# bluepill.net
KiCad netlist of a schematic drawn in EAGLE
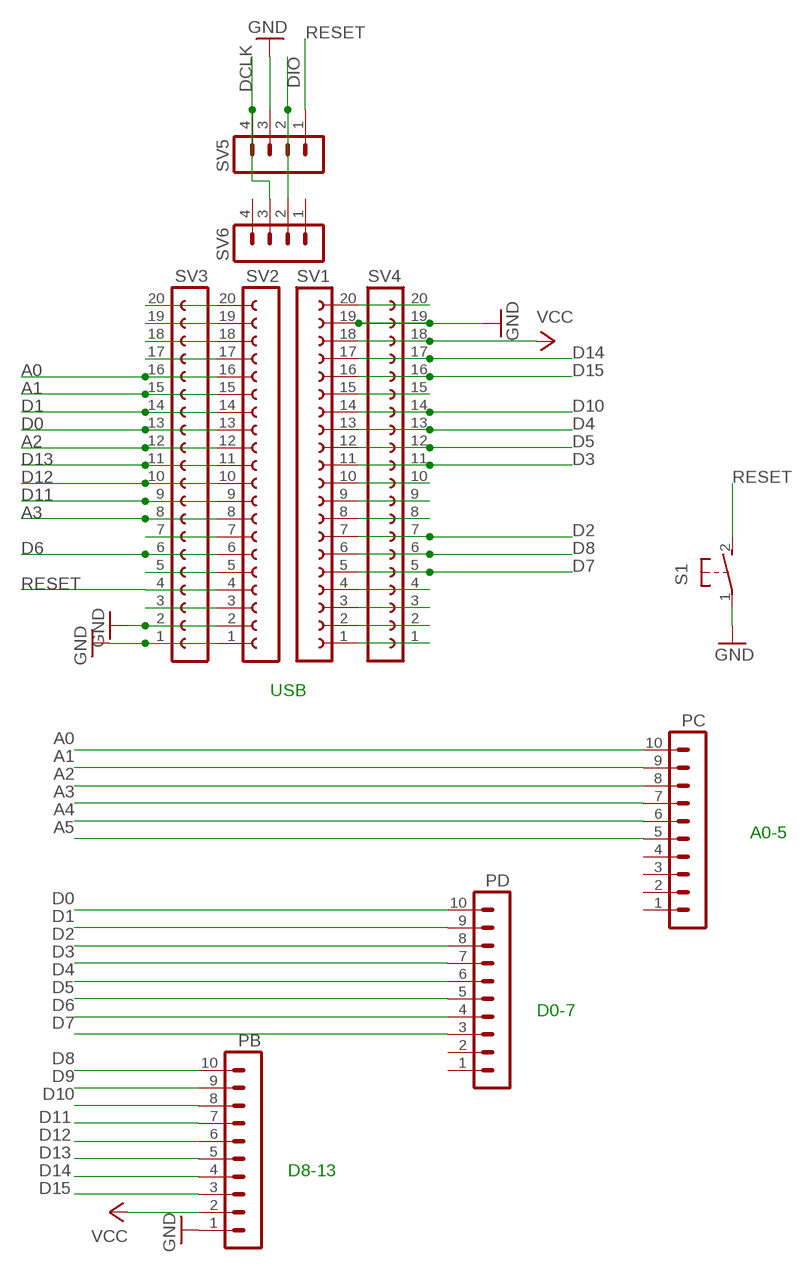
[diagram p0: schematic, sheet 1]

(export (version "E")
  (design (tool "Eeschema 10.0.6"))
  (components
    (comp (ref "PB")
      (value "MA10-1W")
      (footprint "eagle-import:MA10-1W")
      (libsource (lib "eagle-import") (part "MA10-1W"))
    )
    (comp (ref "PC")
      (value "MA10-1W")
      (footprint "eagle-import:MA10-1W")
      (libsource (lib "eagle-import") (part "MA10-1W"))
    )
    (comp (ref "PD")
      (value "MA10-1W")
      (footprint "eagle-import:MA10-1W")
      (libsource (lib "eagle-import") (part "MA10-1W"))
    )
    (comp (ref "S1")
      (value "31-XX")
      (footprint "eagle-import:B3F-31XX")
      (fields (field (name "MPN") "B3F-3100"))
      (libsource (lib "eagle-import") (part "31-XX"))
    )
    (comp (ref "SV1")
      (value "FE20-1")
      (footprint "eagle-import:FE20")
      (libsource (lib "eagle-import") (part "FE20-1"))
    )
    (comp (ref "SV2")
      (value "FE20-1")
      (footprint "eagle-import:FE20")
      (libsource (lib "eagle-import") (part "FE20-1"))
    )
    (comp (ref "SV3")
      (value "FE20-1")
      (footprint "eagle-import:FE20")
      (libsource (lib "eagle-import") (part "FE20-1"))
    )
    (comp (ref "SV4")
      (value "FE20-1")
      (footprint "eagle-import:FE20")
      (libsource (lib "eagle-import") (part "FE20-1"))
    )
    (comp (ref "SV5")
      (value "MA04-1")
      (footprint "eagle-import:MA04-1")
      (libsource (lib "eagle-import") (part "MA04-1"))
    )
    (comp (ref "SV6")
      (value "MA04-1")
      (footprint "eagle-import:MA04-1")
      (libsource (lib "eagle-import") (part "MA04-1"))
    )
  )
  (nets
    (net (code "1") (name "/A0") (class "Default")
      (node (ref "PC") (pin "10") (pinfunction "10_10") (pintype "passive"))
      (node (ref "SV2") (pin "16") (pinfunction "16_16") (pintype "passive"))
      (node (ref "SV3") (pin "16") (pinfunction "16_16") (pintype "passive"))
    )
    (net (code "2") (name "/A1") (class "Default")
      (node (ref "PC") (pin "9") (pinfunction "9_9") (pintype "passive"))
      (node (ref "SV2") (pin "15") (pinfunction "15_15") (pintype "passive"))
      (node (ref "SV3") (pin "15") (pinfunction "15_15") (pintype "passive"))
    )
    (net (code "3") (name "/A2") (class "Default")
      (node (ref "PC") (pin "8") (pinfunction "8_8") (pintype "passive"))
      (node (ref "SV2") (pin "12") (pinfunction "12_12") (pintype "passive"))
      (node (ref "SV3") (pin "12") (pinfunction "12_12") (pintype "passive"))
    )
    (net (code "4") (name "/A3") (class "Default")
      (node (ref "PC") (pin "7") (pinfunction "7_7") (pintype "passive"))
      (node (ref "SV2") (pin "8") (pinfunction "8_8") (pintype "passive"))
      (node (ref "SV3") (pin "8") (pinfunction "8_8") (pintype "passive"))
    )
    (net (code "5") (name "/A4") (class "Default")
      (node (ref "PC") (pin "6") (pinfunction "6_6") (pintype "passive"))
    )
    (net (code "6") (name "/A5") (class "Default")
      (node (ref "PC") (pin "5") (pinfunction "5_5") (pintype "passive"))
    )
    (net (code "7") (name "/D0") (class "Default")
      (node (ref "PD") (pin "10") (pinfunction "10_10") (pintype "passive"))
      (node (ref "SV2") (pin "13") (pinfunction "13_13") (pintype "passive"))
      (node (ref "SV3") (pin "13") (pinfunction "13_13") (pintype "passive"))
    )
    (net (code "8") (name "/D1") (class "Default")
      (node (ref "PD") (pin "9") (pinfunction "9_9") (pintype "passive"))
      (node (ref "SV2") (pin "14") (pinfunction "14_14") (pintype "passive"))
      (node (ref "SV3") (pin "14") (pinfunction "14_14") (pintype "passive"))
    )
    (net (code "9") (name "/D2") (class "Default")
      (node (ref "PD") (pin "8") (pinfunction "8_8") (pintype "passive"))
      (node (ref "SV1") (pin "7") (pinfunction "7_7") (pintype "passive"))
      (node (ref "SV4") (pin "7") (pinfunction "7_7") (pintype "passive"))
    )
    (net (code "10") (name "/D3") (class "Default")
      (node (ref "PD") (pin "7") (pinfunction "7_7") (pintype "passive"))
      (node (ref "SV1") (pin "11") (pinfunction "11_11") (pintype "passive"))
      (node (ref "SV4") (pin "11") (pinfunction "11_11") (pintype "passive"))
    )
    (net (code "11") (name "/D4") (class "Default")
      (node (ref "PD") (pin "6") (pinfunction "6_6") (pintype "passive"))
      (node (ref "SV1") (pin "13") (pinfunction "13_13") (pintype "passive"))
      (node (ref "SV4") (pin "13") (pinfunction "13_13") (pintype "passive"))
    )
    (net (code "12") (name "/D5") (class "Default")
      (node (ref "PD") (pin "5") (pinfunction "5_5") (pintype "passive"))
      (node (ref "SV1") (pin "12") (pinfunction "12_12") (pintype "passive"))
      (node (ref "SV4") (pin "12") (pinfunction "12_12") (pintype "passive"))
    )
    (net (code "13") (name "/D6") (class "Default")
      (node (ref "PD") (pin "4") (pinfunction "4_4") (pintype "passive"))
      (node (ref "SV2") (pin "6") (pinfunction "6_6") (pintype "passive"))
      (node (ref "SV3") (pin "6") (pinfunction "6_6") (pintype "passive"))
    )
    (net (code "14") (name "/D7") (class "Default")
      (node (ref "PD") (pin "3") (pinfunction "3_3") (pintype "passive"))
      (node (ref "SV1") (pin "5") (pinfunction "5_5") (pintype "passive"))
      (node (ref "SV4") (pin "5") (pinfunction "5_5") (pintype "passive"))
    )
    (net (code "15") (name "/D8") (class "Default")
      (node (ref "PB") (pin "10") (pinfunction "10_10") (pintype "passive"))
      (node (ref "SV1") (pin "6") (pinfunction "6_6") (pintype "passive"))
      (node (ref "SV4") (pin "6") (pinfunction "6_6") (pintype "passive"))
    )
    (net (code "16") (name "/D9") (class "Default")
      (node (ref "PB") (pin "9") (pinfunction "9_9") (pintype "passive"))
    )
    (net (code "17") (name "/D10") (class "Default")
      (node (ref "PB") (pin "8") (pinfunction "8_8") (pintype "passive"))
      (node (ref "SV1") (pin "14") (pinfunction "14_14") (pintype "passive"))
      (node (ref "SV4") (pin "14") (pinfunction "14_14") (pintype "passive"))
    )
    (net (code "18") (name "/D11") (class "Default")
      (node (ref "PB") (pin "7") (pinfunction "7_7") (pintype "passive"))
      (node (ref "SV2") (pin "9") (pinfunction "9_9") (pintype "passive"))
      (node (ref "SV3") (pin "9") (pinfunction "9_9") (pintype "passive"))
    )
    (net (code "19") (name "/D12") (class "Default")
      (node (ref "PB") (pin "6") (pinfunction "6_6") (pintype "passive"))
      (node (ref "SV2") (pin "10") (pinfunction "10_10") (pintype "passive"))
      (node (ref "SV3") (pin "10") (pinfunction "10_10") (pintype "passive"))
    )
    (net (code "20") (name "/D13") (class "Default")
      (node (ref "PB") (pin "5") (pinfunction "5_5") (pintype "passive"))
      (node (ref "SV2") (pin "11") (pinfunction "11_11") (pintype "passive"))
      (node (ref "SV3") (pin "11") (pinfunction "11_11") (pintype "passive"))
    )
    (net (code "21") (name "/D14") (class "Default")
      (node (ref "PB") (pin "4") (pinfunction "4_4") (pintype "passive"))
      (node (ref "SV1") (pin "17") (pinfunction "17_17") (pintype "passive"))
      (node (ref "SV4") (pin "17") (pinfunction "17_17") (pintype "passive"))
    )
    (net (code "22") (name "/D15") (class "Default")
      (node (ref "PB") (pin "3") (pinfunction "3_3") (pintype "passive"))
      (node (ref "SV1") (pin "16") (pinfunction "16_16") (pintype "passive"))
      (node (ref "SV4") (pin "16") (pinfunction "16_16") (pintype "passive"))
    )
    (net (code "23") (name "/DCLK") (class "Default")
      (node (ref "SV5") (pin "4") (pinfunction "4_4") (pintype "passive"))
      (node (ref "SV6") (pin "3") (pinfunction "3_3") (pintype "passive"))
    )
    (net (code "24") (name "/DIO") (class "Default")
      (node (ref "SV5") (pin "2") (pinfunction "2_2") (pintype "passive"))
      (node (ref "SV6") (pin "2") (pinfunction "2_2") (pintype "passive"))
    )
    (net (code "25") (name "/RESET") (class "Default")
      (node (ref "S1") (pin "2") (pinfunction "S_2") (pintype "passive"))
      (node (ref "SV2") (pin "4") (pinfunction "4_4") (pintype "passive"))
      (node (ref "SV3") (pin "4") (pinfunction "4_4") (pintype "passive"))
      (node (ref "SV5") (pin "1") (pinfunction "1_1") (pintype "passive"))
    )
    (net (code "26") (name "GND") (class "Default")
      (node (ref "PB") (pin "1") (pinfunction "1_1") (pintype "passive"))
      (node (ref "S1") (pin "1") (pinfunction "P_1") (pintype "passive"))
      (node (ref "SV1") (pin "19") (pinfunction "19_19") (pintype "passive"))
      (node (ref "SV2") (pin "1") (pinfunction "1_1") (pintype "passive"))
      (node (ref "SV2") (pin "2") (pinfunction "2_2") (pintype "passive"))
      (node (ref "SV3") (pin "1") (pinfunction "1_1") (pintype "passive"))
      (node (ref "SV3") (pin "2") (pinfunction "2_2") (pintype "passive"))
      (node (ref "SV4") (pin "19") (pinfunction "19_19") (pintype "passive"))
      (node (ref "SV5") (pin "3") (pinfunction "3_3") (pintype "passive"))
    )
    (net (code "27") (name "Net-(SV1-Pad1)") (class "Default")
      (node (ref "SV1") (pin "1") (pinfunction "1_1") (pintype "passive"))
      (node (ref "SV4") (pin "1") (pinfunction "1_1") (pintype "passive"))
    )
    (net (code "28") (name "Net-(SV1-Pad2)") (class "Default")
      (node (ref "SV1") (pin "2") (pinfunction "2_2") (pintype "passive"))
      (node (ref "SV4") (pin "2") (pinfunction "2_2") (pintype "passive"))
    )
    (net (code "29") (name "Net-(SV1-Pad3)") (class "Default")
      (node (ref "SV1") (pin "3") (pinfunction "3_3") (pintype "passive"))
      (node (ref "SV4") (pin "3") (pinfunction "3_3") (pintype "passive"))
    )
    (net (code "30") (name "Net-(SV1-Pad4)") (class "Default")
      (node (ref "SV1") (pin "4") (pinfunction "4_4") (pintype "passive"))
      (node (ref "SV4") (pin "4") (pinfunction "4_4") (pintype "passive"))
    )
    (net (code "31") (name "Net-(SV1-Pad8)") (class "Default")
      (node (ref "SV1") (pin "8") (pinfunction "8_8") (pintype "passive"))
      (node (ref "SV4") (pin "8") (pinfunction "8_8") (pintype "passive"))
    )
    (net (code "32") (name "Net-(SV1-Pad9)") (class "Default")
      (node (ref "SV1") (pin "9") (pinfunction "9_9") (pintype "passive"))
      (node (ref "SV4") (pin "9") (pinfunction "9_9") (pintype "passive"))
    )
    (net (code "33") (name "Net-(SV1-Pad10)") (class "Default")
      (node (ref "SV1") (pin "10") (pinfunction "10_10") (pintype "passive"))
      (node (ref "SV4") (pin "10") (pinfunction "10_10") (pintype "passive"))
    )
    (net (code "34") (name "Net-(SV1-Pad15)") (class "Default")
      (node (ref "SV1") (pin "15") (pinfunction "15_15") (pintype "passive"))
      (node (ref "SV4") (pin "15") (pinfunction "15_15") (pintype "passive"))
    )
    (net (code "35") (name "Net-(SV1-Pad20)") (class "Default")
      (node (ref "SV1") (pin "20") (pinfunction "20_20") (pintype "passive"))
      (node (ref "SV4") (pin "20") (pinfunction "20_20") (pintype "passive"))
    )
    (net (code "36") (name "Net-(SV2-Pad3)") (class "Default")
      (node (ref "SV2") (pin "3") (pinfunction "3_3") (pintype "passive"))
      (node (ref "SV3") (pin "3") (pinfunction "3_3") (pintype "passive"))
    )
    (net (code "37") (name "Net-(SV2-Pad5)") (class "Default")
      (node (ref "SV2") (pin "5") (pinfunction "5_5") (pintype "passive"))
      (node (ref "SV3") (pin "5") (pinfunction "5_5") (pintype "passive"))
    )
    (net (code "38") (name "Net-(SV2-Pad7)") (class "Default")
      (node (ref "SV2") (pin "7") (pinfunction "7_7") (pintype "passive"))
      (node (ref "SV3") (pin "7") (pinfunction "7_7") (pintype "passive"))
    )
    (net (code "39") (name "Net-(SV2-Pad17)") (class "Default")
      (node (ref "SV2") (pin "17") (pinfunction "17_17") (pintype "passive"))
      (node (ref "SV3") (pin "17") (pinfunction "17_17") (pintype "passive"))
    )
    (net (code "40") (name "Net-(SV2-Pad18)") (class "Default")
      (node (ref "SV2") (pin "18") (pinfunction "18_18") (pintype "passive"))
      (node (ref "SV3") (pin "18") (pinfunction "18_18") (pintype "passive"))
    )
    (net (code "41") (name "Net-(SV2-Pad19)") (class "Default")
      (node (ref "SV2") (pin "19") (pinfunction "19_19") (pintype "passive"))
      (node (ref "SV3") (pin "19") (pinfunction "19_19") (pintype "passive"))
    )
    (net (code "42") (name "Net-(SV2-Pad20)") (class "Default")
      (node (ref "SV2") (pin "20") (pinfunction "20_20") (pintype "passive"))
      (node (ref "SV3") (pin "20") (pinfunction "20_20") (pintype "passive"))
    )
    (net (code "43") (name "VCC") (class "Default")
      (node (ref "PB") (pin "2") (pinfunction "2_2") (pintype "passive"))
      (node (ref "SV1") (pin "18") (pinfunction "18_18") (pintype "passive"))
      (node (ref "SV4") (pin "18") (pinfunction "18_18") (pintype "passive"))
    )
    (net (code "44") (name "unconnected-(PC-Pad1)") (class "Default")
      (node (ref "PC") (pin "1") (pinfunction "1_1") (pintype "passive"))
    )
    (net (code "45") (name "unconnected-(PC-Pad2)") (class "Default")
      (node (ref "PC") (pin "2") (pinfunction "2_2") (pintype "passive"))
    )
    (net (code "46") (name "unconnected-(PC-Pad3)") (class "Default")
      (node (ref "PC") (pin "3") (pinfunction "3_3") (pintype "passive"))
    )
    (net (code "47") (name "unconnected-(PC-Pad4)") (class "Default")
      (node (ref "PC") (pin "4") (pinfunction "4_4") (pintype "passive"))
    )
    (net (code "48") (name "unconnected-(PD-Pad1)") (class "Default")
      (node (ref "PD") (pin "1") (pinfunction "1_1") (pintype "passive"))
    )
    (net (code "49") (name "unconnected-(PD-Pad2)") (class "Default")
      (node (ref "PD") (pin "2") (pinfunction "2_2") (pintype "passive"))
    )
    (net (code "50") (name "unconnected-(SV6-Pad1)") (class "Default")
      (node (ref "SV6") (pin "1") (pinfunction "1_1") (pintype "passive"))
    )
    (net (code "51") (name "unconnected-(SV6-Pad4)") (class "Default")
      (node (ref "SV6") (pin "4") (pinfunction "4_4") (pintype "passive"))
    )
  )
)
